# USART.net
KiCad netlist of a schematic drawn in Altium Designer
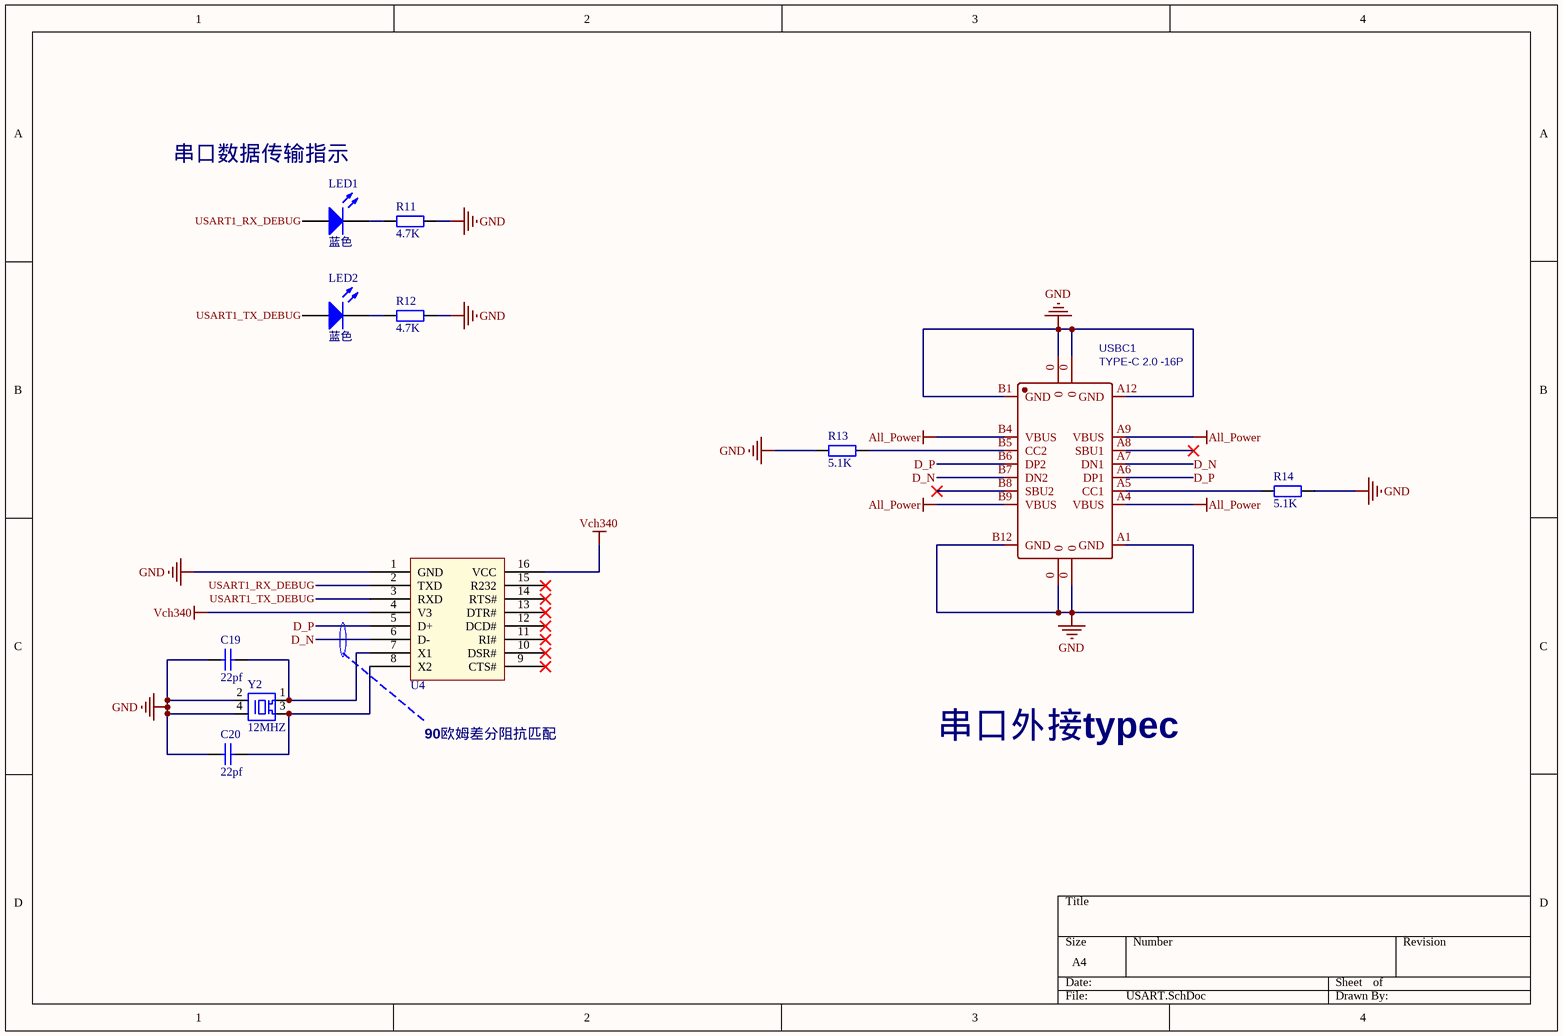
[diagram p0: USART.SchDoc]

(export (version "E")
  (design (tool "Eeschema 10.0.6"))
  (components
    (comp (ref "C19")
      (value "22pf")
      (footprint "C0603_M")
      (description "贴片电容")
      (libsource (lib "cdud开发板") (part "C"))
    )
    (comp (ref "C20")
      (value "22pf")
      (footprint "C0603_M")
      (description "贴片电容")
      (libsource (lib "cdud开发板") (part "C"))
    )
    (comp (ref "LED1")
      (value "蓝色")
      (footprint "LED0603_B")
      (description "贴片LED")
      (libsource (lib "0.3 - LED发光二极管-IR二极管_接收管-光耦") (part "LED"))
    )
    (comp (ref "LED2")
      (value "蓝色")
      (footprint "LED0603_B")
      (description "贴片LED")
      (libsource (lib "0.3 - LED发光二极管-IR二极管_接收管-光耦") (part "LED"))
    )
    (comp (ref "R11")
      (value "4.7K")
      (footprint "R0603_M")
      (description "贴片电阻")
      (libsource (lib "cdud开发板") (part "R"))
    )
    (comp (ref "R12")
      (value "4.7K")
      (footprint "R0603_M")
      (description "贴片电阻")
      (libsource (lib "cdud开发板") (part "R"))
    )
    (comp (ref "R13")
      (value "5.1K")
      (footprint "R0603_M")
      (description "贴片电阻")
      (fields (field (name "版权归属") "来自淘宝 ID：黄晶宝石"))
      (libsource (lib "0.1 - 电阻-电容-电感") (part "R"))
    )
    (comp (ref "R14")
      (value "5.1K")
      (footprint "R0603_M")
      (description "贴片电阻")
      (fields (field (name "版权归属") "来自淘宝 ID：黄晶宝石"))
      (libsource (lib "0.1 - 电阻-电容-电感") (part "R"))
    )
    (comp (ref "U4")
      (value "CH340G")
      (footprint "SOP16N_N")
      (libsource (lib "1.9 - CH340系列编程器芯片") (part "CH340G"))
    )
    (comp (ref "USBC1")
      (value "TYPE-C 2.0 -16P")
      (footprint "USB-C-SMD_TYPE-C-USB-5")
      (description "USB2.0 Type-C 母座 16Pin")
      (libsource (lib "0.8 - 以太网-音频-USB插座") (part "USB2.0 Type-C 16Pin母座"))
    )
    (comp (ref "Y2") (value "12MHZ") (footprint "OSC 3225-4P") (libsource (lib "cdud开发板") (part "jinzheng")))
  )
  (nets
    (net (code "1") (name "/D_N") (class "Default")
      (node (ref "U4") (pin "6") (pinfunction "D-_6") (pintype "passive"))
      (node (ref "USBC1") (pin "A7") (pinfunction "DN1_A7") (pintype "passive"))
      (node (ref "USBC1") (pin "B7") (pinfunction "DN2_B7") (pintype "passive"))
    )
    (net (code "2") (name "/D_P") (class "Default")
      (node (ref "U4") (pin "5") (pinfunction "D+_5") (pintype "passive"))
      (node (ref "USBC1") (pin "A6") (pinfunction "DP1_A6") (pintype "passive"))
      (node (ref "USBC1") (pin "B6") (pinfunction "DP2_B6") (pintype "passive"))
    )
    (net (code "3") (name "/USART1_RX_DEBUG") (class "Default")
      (node (ref "LED1") (pin "1") (pinfunction "A_1") (pintype "passive"))
      (node (ref "U4") (pin "2") (pinfunction "TXD_2") (pintype "passive"))
    )
    (net (code "4") (name "/USART1_TX_DEBUG") (class "Default")
      (node (ref "LED2") (pin "1") (pinfunction "A_1") (pintype "passive"))
      (node (ref "U4") (pin "3") (pinfunction "RXD_3") (pintype "passive"))
    )
    (net (code "5") (name "All_Power") (class "Default")
      (node (ref "USBC1") (pin "A4") (pinfunction "VBUS_A4") (pintype "passive"))
      (node (ref "USBC1") (pin "A9") (pinfunction "VBUS_A9") (pintype "passive"))
      (node (ref "USBC1") (pin "B4") (pinfunction "VBUS_B4") (pintype "passive"))
      (node (ref "USBC1") (pin "B9") (pinfunction "VBUS_B9") (pintype "passive"))
    )
    (net (code "6") (name "GND") (class "Default")
      (node (ref "C19") (pin "1") (pinfunction "1_1") (pintype "passive"))
      (node (ref "C20") (pin "1") (pinfunction "1_1") (pintype "passive"))
      (node (ref "R11") (pin "1") (pinfunction "1_1") (pintype "passive"))
      (node (ref "R12") (pin "1") (pinfunction "1_1") (pintype "passive"))
      (node (ref "R13") (pin "1") (pinfunction "1_1") (pintype "passive"))
      (node (ref "R14") (pin "1") (pinfunction "1_1") (pintype "passive"))
      (node (ref "U4") (pin "1") (pinfunction "GND_1") (pintype "passive"))
      (node (ref "USBC1") (pin "0") (pinfunction "0_0") (pintype "passive"))
      (node (ref "USBC1") (pin "A1") (pinfunction "GND_A1") (pintype "passive"))
      (node (ref "USBC1") (pin "A12") (pinfunction "GND_A12") (pintype "passive"))
      (node (ref "USBC1") (pin "B1") (pinfunction "GND_B1") (pintype "passive"))
      (node (ref "USBC1") (pin "B12") (pinfunction "GND_B12") (pintype "passive"))
      (node (ref "Y2") (pin "2") (pinfunction "GND_2") (pintype "passive"))
      (node (ref "Y2") (pin "4") (pinfunction "GND_4") (pintype "passive"))
    )
    (net (code "7") (name "Net-(LED1-K)") (class "Default")
      (node (ref "LED1") (pin "2") (pinfunction "K_2") (pintype "passive"))
      (node (ref "R11") (pin "2") (pinfunction "2_2") (pintype "passive"))
    )
    (net (code "8") (name "Net-(LED2-K)") (class "Default")
      (node (ref "LED2") (pin "2") (pinfunction "K_2") (pintype "passive"))
      (node (ref "R12") (pin "2") (pinfunction "2_2") (pintype "passive"))
    )
    (net (code "9") (name "Net-(U4-X1)") (class "Default")
      (node (ref "C19") (pin "2") (pinfunction "2_2") (pintype "passive"))
      (node (ref "U4") (pin "7") (pinfunction "X1_7") (pintype "passive"))
      (node (ref "Y2") (pin "1") (pinfunction "XTAL1_1") (pintype "passive"))
    )
    (net (code "10") (name "Net-(U4-X2)") (class "Default")
      (node (ref "C20") (pin "2") (pinfunction "2_2") (pintype "passive"))
      (node (ref "U4") (pin "8") (pinfunction "X2_8") (pintype "passive"))
      (node (ref "Y2") (pin "3") (pinfunction "XTAL3_3") (pintype "passive"))
    )
    (net (code "11") (name "Net-(USBC1-CC1)") (class "Default")
      (node (ref "R14") (pin "2") (pinfunction "2_2") (pintype "passive"))
      (node (ref "USBC1") (pin "A5") (pinfunction "CC1_A5") (pintype "passive"))
    )
    (net (code "12") (name "Net-(USBC1-CC2)") (class "Default")
      (node (ref "R13") (pin "2") (pinfunction "2_2") (pintype "passive"))
      (node (ref "USBC1") (pin "B5") (pinfunction "CC2_B5") (pintype "passive"))
    )
    (net (code "13") (name "Vch340") (class "Default")
      (node (ref "U4") (pin "16") (pinfunction "VCC_16") (pintype "passive"))
      (node (ref "U4") (pin "4") (pinfunction "V3_4") (pintype "passive"))
    )
    (net (code "14") (name "unconnected-(U4-CTS#-Pad9)") (class "Default")
      (node (ref "U4") (pin "9") (pinfunction "CTS#_9") (pintype "passive+no_connect"))
    )
    (net (code "15") (name "unconnected-(U4-DCD#-Pad12)") (class "Default")
      (node (ref "U4") (pin "12") (pinfunction "DCD#_12") (pintype "passive+no_connect"))
    )
    (net (code "16") (name "unconnected-(U4-DSR#-Pad10)") (class "Default")
      (node (ref "U4") (pin "10") (pinfunction "DSR#_10") (pintype "passive+no_connect"))
    )
    (net (code "17") (name "unconnected-(U4-DTR#-Pad13)") (class "Default")
      (node (ref "U4") (pin "13") (pinfunction "DTR#_13") (pintype "passive+no_connect"))
    )
    (net (code "18") (name "unconnected-(U4-R232-Pad15)") (class "Default")
      (node (ref "U4") (pin "15") (pinfunction "R232_15") (pintype "passive+no_connect"))
    )
    (net (code "19") (name "unconnected-(U4-RI#-Pad11)") (class "Default")
      (node (ref "U4") (pin "11") (pinfunction "RI#_11") (pintype "passive+no_connect"))
    )
    (net (code "20") (name "unconnected-(U4-RTS#-Pad14)") (class "Default")
      (node (ref "U4") (pin "14") (pinfunction "RTS#_14") (pintype "passive+no_connect"))
    )
    (net (code "21") (name "unconnected-(USBC1-SBU1-PadA8)") (class "Default")
      (node (ref "USBC1") (pin "A8") (pinfunction "SBU1_A8") (pintype "passive+no_connect"))
    )
    (net (code "22") (name "unconnected-(USBC1-SBU2-PadB8)") (class "Default")
      (node (ref "USBC1") (pin "B8") (pinfunction "SBU2_B8") (pintype "passive+no_connect"))
    )
  )
)
